# Micro_RC_Receiver_HP.net
KiCad netlist of a schematic drawn in EAGLE
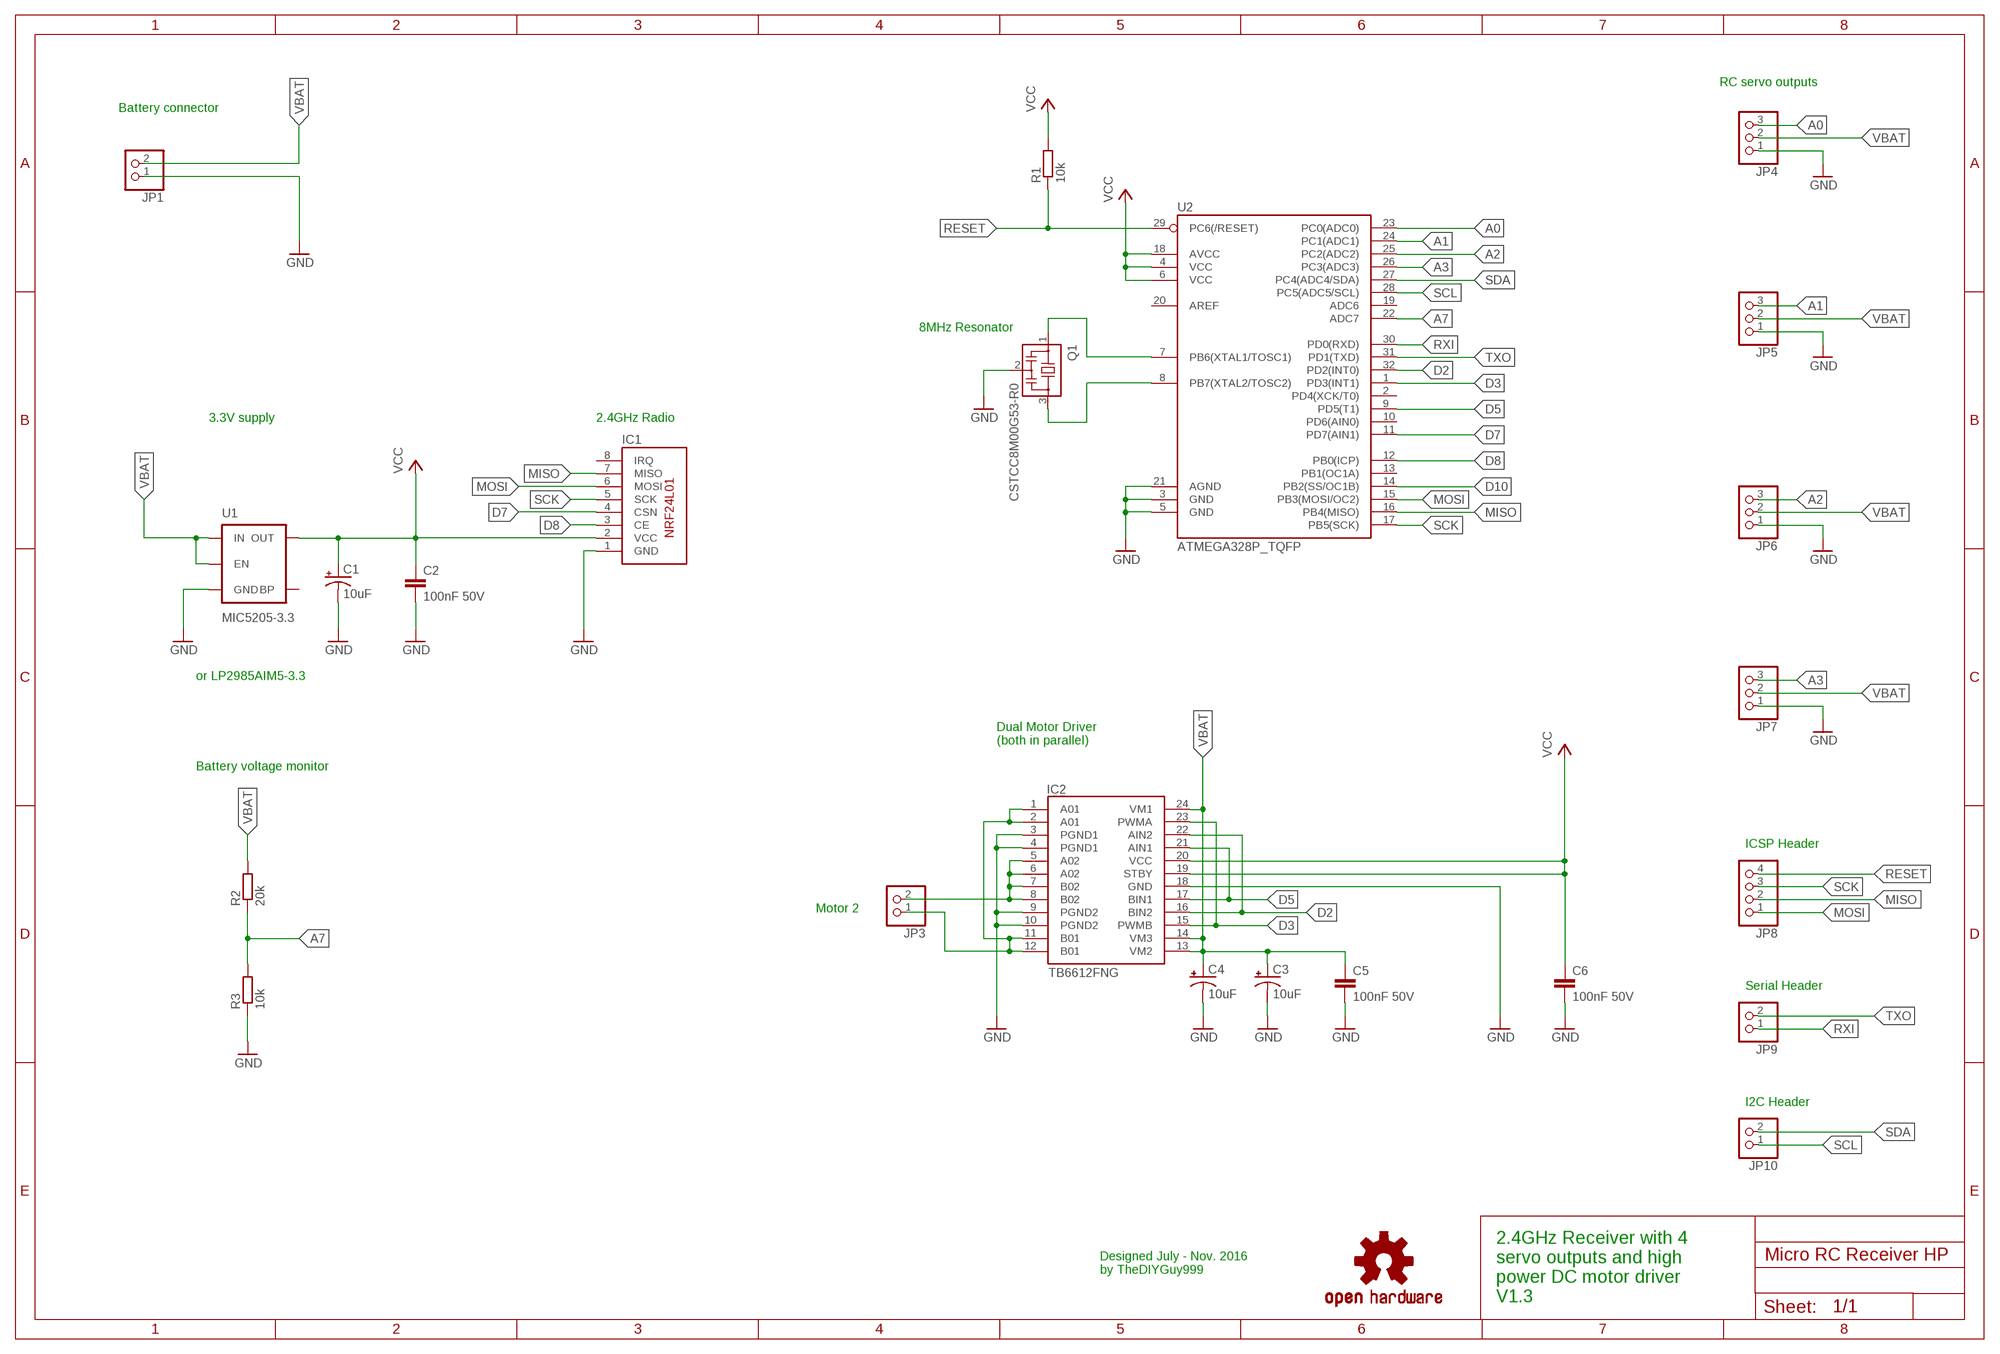
[diagram p0: schematic, sheet 1]

(export (version "E")
  (design (tool "Eeschema 10.0.6"))
  (components
    (comp (ref "C1")
      (value "10uF")
      (footprint "eagle-import:EIA3216")
      (libsource (lib "eagle-import") (part "10UF-16V-10%(TANT)"))
    )
    (comp (ref "C2")
      (value "100nF 50V")
      (footprint "eagle-import:C0805")
      (libsource (lib "eagle-import") (part "C-EUC0805"))
    )
    (comp (ref "C3")
      (value "10uF")
      (footprint "eagle-import:EIA3216")
      (libsource (lib "eagle-import") (part "10UF-16V-10%(TANT)"))
    )
    (comp (ref "C4")
      (value "10uF")
      (footprint "eagle-import:EIA3216")
      (libsource (lib "eagle-import") (part "10UF-16V-10%(TANT)"))
    )
    (comp (ref "C5")
      (value "100nF 50V")
      (footprint "eagle-import:C0805")
      (libsource (lib "eagle-import") (part "C-EUC0805"))
    )
    (comp (ref "C6")
      (value "100nF 50V")
      (footprint "eagle-import:C0805")
      (libsource (lib "eagle-import") (part "C-EUC0805"))
    )
    (comp (ref "IC1")
      (value "NRF24L01SMD")
      (footprint "eagle-import:NRF24L01_SMD")
      (libsource (lib "eagle-import") (part "NRF24L01SMD"))
    )
    (comp (ref "IC2")
      (value "TB6612FNG")
      (footprint "eagle-import:SSOP24")
      (libsource (lib "eagle-import") (part "TB6612FNG"))
    )
    (comp (ref "JP1")
      (value "PINHD-1X2")
      (footprint "eagle-import:1X02")
      (libsource (lib "eagle-import") (part "PINHD-1X2"))
    )
    (comp (ref "JP3")
      (value "PINHD-1X2")
      (footprint "eagle-import:1X02")
      (libsource (lib "eagle-import") (part "PINHD-1X2"))
    )
    (comp (ref "JP4")
      (value "PINHD-1X3")
      (footprint "eagle-import:1X03")
      (libsource (lib "eagle-import") (part "PINHD-1X3"))
    )
    (comp (ref "JP5")
      (value "PINHD-1X3")
      (footprint "eagle-import:1X03")
      (libsource (lib "eagle-import") (part "PINHD-1X3"))
    )
    (comp (ref "JP6")
      (value "PINHD-1X3")
      (footprint "eagle-import:1X03")
      (libsource (lib "eagle-import") (part "PINHD-1X3"))
    )
    (comp (ref "JP7")
      (value "PINHD-1X3")
      (footprint "eagle-import:1X03")
      (libsource (lib "eagle-import") (part "PINHD-1X3"))
    )
    (comp (ref "JP8")
      (value "PINHD-1X4")
      (footprint "eagle-import:1X04")
      (libsource (lib "eagle-import") (part "PINHD-1X4"))
    )
    (comp (ref "JP9")
      (value "PINHD-1X2")
      (footprint "eagle-import:1X02")
      (libsource (lib "eagle-import") (part "PINHD-1X2"))
    )
    (comp (ref "JP10")
      (value "PINHD-1X2")
      (footprint "eagle-import:1X02")
      (libsource (lib "eagle-import") (part "PINHD-1X2"))
    )
    (comp (ref "LOGO1")
      (value "OSHW-LOGOS")
      (footprint "eagle-import:OSHW-LOGO-S")
      (libsource (lib "eagle-import") (part "OSHW-LOGOS"))
    )
    (comp (ref "Q1")
      (value "CSTCC8M00G53-R0")
      (footprint "eagle-import:CSTCC")
      (libsource (lib "eagle-import") (part "CSTCC8M00G53-R0"))
    )
    (comp (ref "R1")
      (value "10k")
      (footprint "eagle-import:R0805")
      (libsource (lib "eagle-import") (part "R-EU_R0805"))
    )
    (comp (ref "R2")
      (value "20k")
      (footprint "eagle-import:R0805")
      (libsource (lib "eagle-import") (part "R-EU_R0805"))
    )
    (comp (ref "R3")
      (value "10k")
      (footprint "eagle-import:R0805")
      (libsource (lib "eagle-import") (part "R-EU_R0805"))
    )
    (comp (ref "U1")
      (value "MIC5205-3.3")
      (footprint "eagle-import:SOT23-5")
      (libsource (lib "eagle-import") (part "MIC52053.3V"))
    )
    (comp (ref "U2")
      (value "ATMEGA328P_TQFP")
      (footprint "eagle-import:TQFP32-08")
      (libsource (lib "eagle-import") (part "ATMEGA328P_TQFP"))
    )
  )
  (nets
    (net (code "1") (name "A0") (class "Default")
      (node (ref "JP4") (pin "3") (pinfunction "3_3") (pintype "passive"))
      (node (ref "U2") (pin "23") (pinfunction "PC0(ADC0)_23") (pintype "bidirectional"))
    )
    (net (code "2") (name "A1") (class "Default")
      (node (ref "JP5") (pin "3") (pinfunction "3_3") (pintype "passive"))
      (node (ref "U2") (pin "24") (pinfunction "PC1(ADC1)_24") (pintype "bidirectional"))
    )
    (net (code "3") (name "A2") (class "Default")
      (node (ref "JP6") (pin "3") (pinfunction "3_3") (pintype "passive"))
      (node (ref "U2") (pin "25") (pinfunction "PC2(ADC2)_25") (pintype "bidirectional"))
    )
    (net (code "4") (name "A3") (class "Default")
      (node (ref "JP7") (pin "3") (pinfunction "3_3") (pintype "passive"))
      (node (ref "U2") (pin "26") (pinfunction "PC3(ADC3)_26") (pintype "bidirectional"))
    )
    (net (code "5") (name "A7") (class "Default")
      (node (ref "R2") (pin "1") (pinfunction "1_1") (pintype "passive"))
      (node (ref "R3") (pin "2") (pinfunction "2_2") (pintype "passive"))
      (node (ref "U2") (pin "22") (pinfunction "ADC7_22") (pintype "bidirectional"))
    )
    (net (code "6") (name "D2") (class "Default")
      (node (ref "IC2") (pin "16") (pinfunction "BIN2_16") (pintype "bidirectional"))
      (node (ref "IC2") (pin "22") (pinfunction "AIN2_22") (pintype "bidirectional"))
      (node (ref "U2") (pin "32") (pinfunction "PD2(INT0)_32") (pintype "bidirectional"))
    )
    (net (code "7") (name "D3") (class "Default")
      (node (ref "IC2") (pin "15") (pinfunction "PWMB_15") (pintype "bidirectional"))
      (node (ref "IC2") (pin "23") (pinfunction "PWMA_23") (pintype "bidirectional"))
      (node (ref "U2") (pin "1") (pinfunction "PD3(INT1)_1") (pintype "bidirectional"))
    )
    (net (code "8") (name "D5") (class "Default")
      (node (ref "IC2") (pin "17") (pinfunction "BIN1_17") (pintype "bidirectional"))
      (node (ref "IC2") (pin "21") (pinfunction "AIN1_21") (pintype "bidirectional"))
      (node (ref "U2") (pin "9") (pinfunction "PD5(T1)_9") (pintype "bidirectional"))
    )
    (net (code "9") (name "D7") (class "Default")
      (node (ref "IC1") (pin "4") (pinfunction "CSN_4") (pintype "bidirectional"))
      (node (ref "U2") (pin "11") (pinfunction "PD7(AIN1)_11") (pintype "bidirectional"))
    )
    (net (code "10") (name "D8") (class "Default")
      (node (ref "IC1") (pin "3") (pinfunction "CE_3") (pintype "bidirectional"))
      (node (ref "U2") (pin "12") (pinfunction "PB0(ICP)_12") (pintype "bidirectional"))
    )
    (net (code "11") (name "D10") (class "Default")
      (node (ref "U2") (pin "14") (pinfunction "PB2(SS/OC1B)_14") (pintype "bidirectional"))
    )
    (net (code "12") (name "GND") (class "Default")
      (node (ref "C1") (pin "C") (pinfunction "-_C") (pintype "passive"))
      (node (ref "C2") (pin "2") (pinfunction "2_2") (pintype "passive"))
      (node (ref "C3") (pin "C") (pinfunction "-_C") (pintype "passive"))
      (node (ref "C4") (pin "C") (pinfunction "-_C") (pintype "passive"))
      (node (ref "C5") (pin "2") (pinfunction "2_2") (pintype "passive"))
      (node (ref "C6") (pin "2") (pinfunction "2_2") (pintype "passive"))
      (node (ref "IC1") (pin "1") (pinfunction "GND_1") (pintype "bidirectional"))
      (node (ref "IC2") (pin "10") (pinfunction "PGND2_10") (pintype "bidirectional"))
      (node (ref "IC2") (pin "18") (pinfunction "GND_18") (pintype "bidirectional"))
      (node (ref "IC2") (pin "3") (pinfunction "PGND1_3") (pintype "bidirectional"))
      (node (ref "IC2") (pin "4") (pinfunction "PGND1_4") (pintype "bidirectional"))
      (node (ref "IC2") (pin "9") (pinfunction "PGND2_9") (pintype "bidirectional"))
      (node (ref "JP1") (pin "1") (pinfunction "1_1") (pintype "passive"))
      (node (ref "JP4") (pin "1") (pinfunction "1_1") (pintype "passive"))
      (node (ref "JP5") (pin "1") (pinfunction "1_1") (pintype "passive"))
      (node (ref "JP6") (pin "1") (pinfunction "1_1") (pintype "passive"))
      (node (ref "JP7") (pin "1") (pinfunction "1_1") (pintype "passive"))
      (node (ref "Q1") (pin "2") (pinfunction "2_2") (pintype "passive"))
      (node (ref "R3") (pin "1") (pinfunction "1_1") (pintype "passive"))
      (node (ref "U1") (pin "2") (pinfunction "GND_2") (pintype "input"))
      (node (ref "U2") (pin "21") (pinfunction "AGND_21") (pintype "bidirectional"))
      (node (ref "U2") (pin "3") (pinfunction "GND_3") (pintype "bidirectional"))
      (node (ref "U2") (pin "5") (pinfunction "GND_5") (pintype "bidirectional"))
    )
    (net (code "13") (name "MISO") (class "Default")
      (node (ref "IC1") (pin "7") (pinfunction "MISO_7") (pintype "bidirectional"))
      (node (ref "JP8") (pin "2") (pinfunction "2_2") (pintype "passive"))
      (node (ref "U2") (pin "16") (pinfunction "PB4(MISO)_16") (pintype "bidirectional"))
    )
    (net (code "14") (name "MOSI") (class "Default")
      (node (ref "IC1") (pin "6") (pinfunction "MOSI_6") (pintype "bidirectional"))
      (node (ref "JP8") (pin "1") (pinfunction "1_1") (pintype "passive"))
      (node (ref "U2") (pin "15") (pinfunction "PB3(MOSI/OC2)_15") (pintype "bidirectional"))
    )
    (net (code "15") (name "Net-(IC2-A01-Pad1)") (class "Default")
      (node (ref "IC2") (pin "1") (pinfunction "A01_1") (pintype "bidirectional"))
      (node (ref "IC2") (pin "11") (pinfunction "B01_11") (pintype "bidirectional"))
      (node (ref "IC2") (pin "12") (pinfunction "B01_12") (pintype "bidirectional"))
      (node (ref "IC2") (pin "2") (pinfunction "A01_2") (pintype "bidirectional"))
      (node (ref "JP3") (pin "1") (pinfunction "1_1") (pintype "passive"))
    )
    (net (code "16") (name "Net-(IC2-A02-Pad5)") (class "Default")
      (node (ref "IC2") (pin "5") (pinfunction "A02_5") (pintype "bidirectional"))
      (node (ref "IC2") (pin "6") (pinfunction "A02_6") (pintype "bidirectional"))
      (node (ref "IC2") (pin "7") (pinfunction "B02_7") (pintype "bidirectional"))
      (node (ref "IC2") (pin "8") (pinfunction "B02_8") (pintype "bidirectional"))
      (node (ref "JP3") (pin "2") (pinfunction "2_2") (pintype "passive"))
    )
    (net (code "17") (name "Net-(U2-PB6(XTAL1{slash}TOSC1))") (class "Default")
      (node (ref "Q1") (pin "1") (pinfunction "1_1") (pintype "passive"))
      (node (ref "U2") (pin "7") (pinfunction "PB6(XTAL1/TOSC1)_7") (pintype "bidirectional"))
    )
    (net (code "18") (name "Net-(U2-PB7(XTAL2{slash}TOSC2))") (class "Default")
      (node (ref "Q1") (pin "3") (pinfunction "3_3") (pintype "passive"))
      (node (ref "U2") (pin "8") (pinfunction "PB7(XTAL2/TOSC2)_8") (pintype "bidirectional"))
    )
    (net (code "19") (name "RESET") (class "Default")
      (node (ref "JP8") (pin "4") (pinfunction "4_4") (pintype "passive"))
      (node (ref "R1") (pin "1") (pinfunction "1_1") (pintype "passive"))
      (node (ref "U2") (pin "29") (pinfunction "PC6(/RESET)_29") (pintype "bidirectional"))
    )
    (net (code "20") (name "RXI") (class "Default")
      (node (ref "JP9") (pin "1") (pinfunction "1_1") (pintype "passive"))
      (node (ref "U2") (pin "30") (pinfunction "PD0(RXD)_30") (pintype "bidirectional"))
    )
    (net (code "21") (name "SCK") (class "Default")
      (node (ref "IC1") (pin "5") (pinfunction "SCK_5") (pintype "bidirectional"))
      (node (ref "JP8") (pin "3") (pinfunction "3_3") (pintype "passive"))
      (node (ref "U2") (pin "17") (pinfunction "PB5(SCK)_17") (pintype "bidirectional"))
    )
    (net (code "22") (name "SCL") (class "Default")
      (node (ref "JP10") (pin "1") (pinfunction "1_1") (pintype "passive"))
      (node (ref "U2") (pin "28") (pinfunction "PC5(ADC5/SCL)_28") (pintype "bidirectional"))
    )
    (net (code "23") (name "SDA") (class "Default")
      (node (ref "JP10") (pin "2") (pinfunction "2_2") (pintype "passive"))
      (node (ref "U2") (pin "27") (pinfunction "PC4(ADC4/SDA)_27") (pintype "bidirectional"))
    )
    (net (code "24") (name "TXO") (class "Default")
      (node (ref "JP9") (pin "2") (pinfunction "2_2") (pintype "passive"))
      (node (ref "U2") (pin "31") (pinfunction "PD1(TXD)_31") (pintype "bidirectional"))
    )
    (net (code "25") (name "VBAT") (class "Default")
      (node (ref "C3") (pin "A") (pinfunction "+_A") (pintype "passive"))
      (node (ref "C4") (pin "A") (pinfunction "+_A") (pintype "passive"))
      (node (ref "C5") (pin "1") (pinfunction "1_1") (pintype "passive"))
      (node (ref "IC2") (pin "13") (pinfunction "VM2_13") (pintype "bidirectional"))
      (node (ref "IC2") (pin "14") (pinfunction "VM3_14") (pintype "bidirectional"))
      (node (ref "IC2") (pin "24") (pinfunction "VM1_24") (pintype "bidirectional"))
      (node (ref "JP1") (pin "2") (pinfunction "2_2") (pintype "passive"))
      (node (ref "JP4") (pin "2") (pinfunction "2_2") (pintype "passive"))
      (node (ref "JP5") (pin "2") (pinfunction "2_2") (pintype "passive"))
      (node (ref "JP6") (pin "2") (pinfunction "2_2") (pintype "passive"))
      (node (ref "JP7") (pin "2") (pinfunction "2_2") (pintype "passive"))
      (node (ref "R2") (pin "2") (pinfunction "2_2") (pintype "passive"))
      (node (ref "U1") (pin "1") (pinfunction "IN_1") (pintype "input"))
      (node (ref "U1") (pin "3") (pinfunction "EN_3") (pintype "input"))
    )
    (net (code "26") (name "VCC") (class "Default")
      (node (ref "C1") (pin "A") (pinfunction "+_A") (pintype "passive"))
      (node (ref "C2") (pin "1") (pinfunction "1_1") (pintype "passive"))
      (node (ref "C6") (pin "1") (pinfunction "1_1") (pintype "passive"))
      (node (ref "IC1") (pin "2") (pinfunction "VCC_2") (pintype "bidirectional"))
      (node (ref "IC2") (pin "19") (pinfunction "STBY_19") (pintype "bidirectional"))
      (node (ref "IC2") (pin "20") (pinfunction "VCC_20") (pintype "bidirectional"))
      (node (ref "R1") (pin "2") (pinfunction "2_2") (pintype "passive"))
      (node (ref "U1") (pin "5") (pinfunction "OUT_5") (pintype "passive"))
      (node (ref "U2") (pin "18") (pinfunction "AVCC_18") (pintype "bidirectional"))
      (node (ref "U2") (pin "4") (pinfunction "VCC_4") (pintype "bidirectional"))
      (node (ref "U2") (pin "6") (pinfunction "VCC_6") (pintype "bidirectional"))
    )
    (net (code "27") (name "unconnected-(IC1-IRQ-Pad8)") (class "Default")
      (node (ref "IC1") (pin "8") (pinfunction "IRQ_8") (pintype "bidirectional"))
    )
    (net (code "28") (name "unconnected-(U1-BP-Pad4)") (class "Default")
      (node (ref "U1") (pin "4") (pinfunction "BP_4") (pintype "input"))
    )
    (net (code "29") (name "unconnected-(U2-ADC6-Pad19)") (class "Default")
      (node (ref "U2") (pin "19") (pinfunction "ADC6_19") (pintype "bidirectional"))
    )
    (net (code "30") (name "unconnected-(U2-AREF-Pad20)") (class "Default")
      (node (ref "U2") (pin "20") (pinfunction "AREF_20") (pintype "bidirectional"))
    )
    (net (code "31") (name "unconnected-(U2-PB1(OC1A)-Pad13)") (class "Default")
      (node (ref "U2") (pin "13") (pinfunction "PB1(OC1A)_13") (pintype "bidirectional"))
    )
    (net (code "32") (name "unconnected-(U2-PD4(XCK{slash}T0)-Pad2)") (class "Default")
      (node (ref "U2") (pin "2") (pinfunction "PD4(XCK/T0)_2") (pintype "bidirectional"))
    )
    (net (code "33") (name "unconnected-(U2-PD6(AIN0)-Pad10)") (class "Default")
      (node (ref "U2") (pin "10") (pinfunction "PD6(AIN0)_10") (pintype "bidirectional"))
    )
  )
)
